# Sheet1.net
KiCad netlist of a schematic drawn in Altium Designer
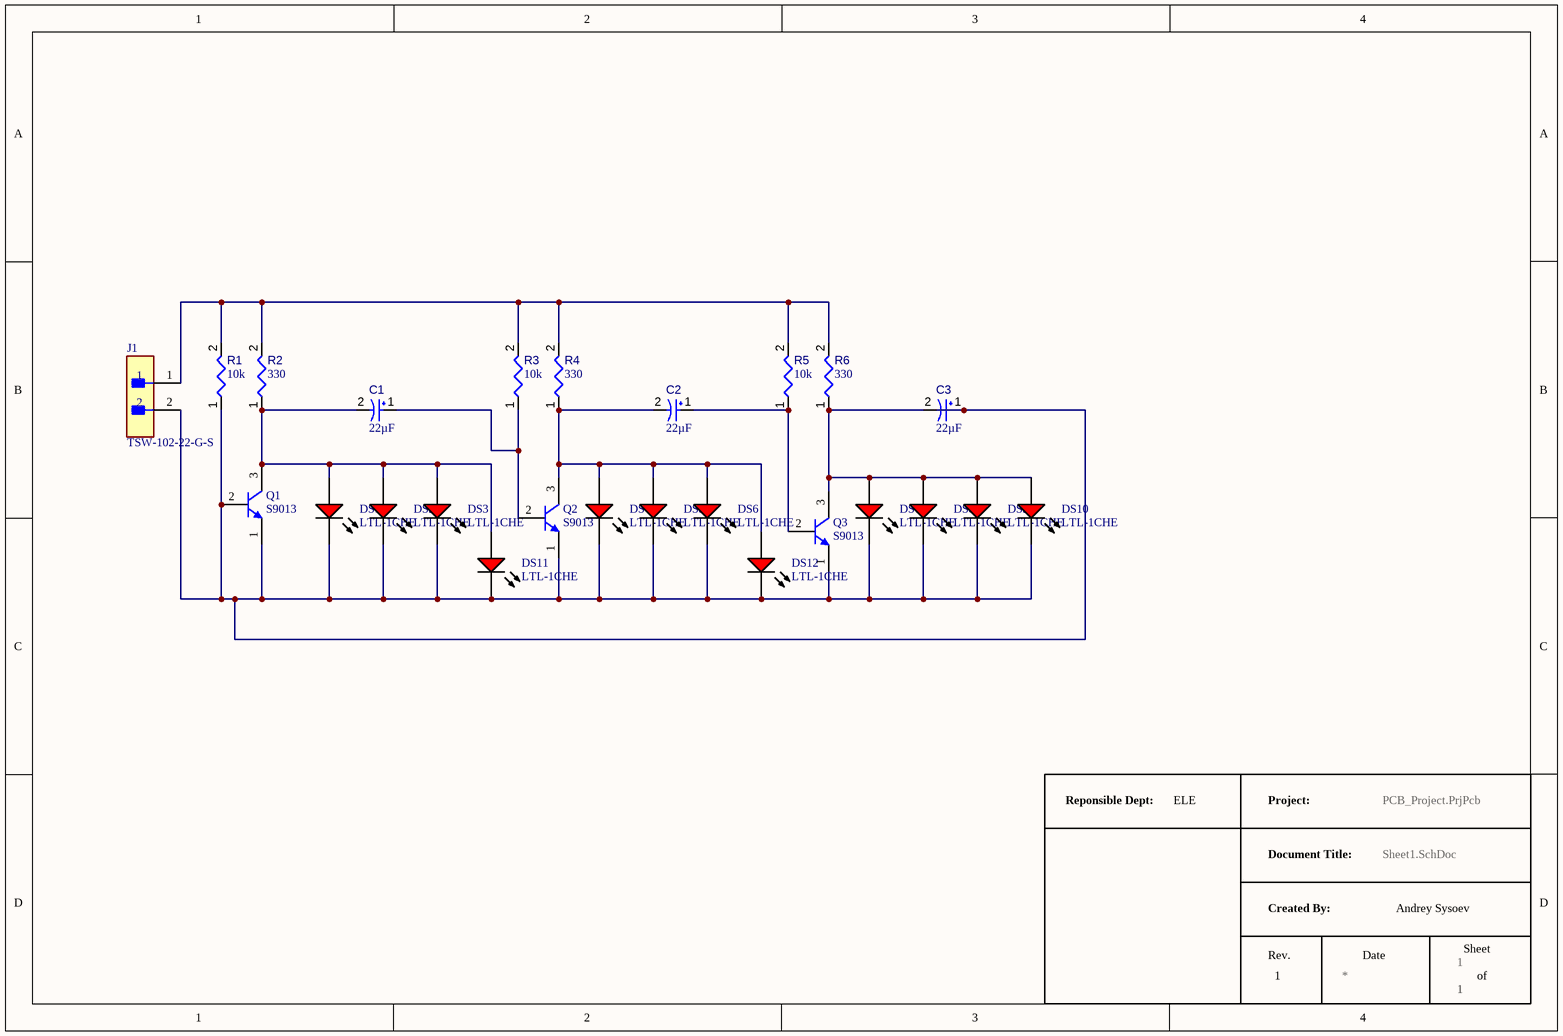
[diagram p0: Sheet1.SchDoc]

(export (version "E")
  (design (tool "Eeschema 10.0.6"))
  (components
    (comp (ref "*") (value "HSHL title block") (libsource (lib "Schlib1") (part "HSHL title block")))
    (comp (ref "C1")
      (value "22µF")
      (footprint "CAPPR55-250-1120X630X1220")
      (description "Aluminum Electrolytic Capacitor, 22 uF, +/- 20%, 100 V, -40 to 85 degC, 2-Pin THD, RoHS, Bulk")
      (fields (field (name "MANUFACTURER") "Panasonic") (field (name "TOLERANCE") "20%"))
      (libsource (lib "Andrey Sysoev") (part "CAP-P-2"))
    )
    (comp (ref "C2")
      (value "22µF")
      (footprint "CAPPR55-250-1120X630X1220")
      (description "Aluminum Electrolytic Capacitor, 22 uF, +/- 20%, 100 V, -40 to 85 degC, 2-Pin THD, RoHS, Bulk")
      (fields (field (name "MANUFACTURER") "Panasonic") (field (name "TOLERANCE") "20%"))
      (libsource (lib "Andrey Sysoev") (part "CAP-P-2"))
    )
    (comp (ref "C3")
      (value "22µF")
      (footprint "CAPPR55-250-1120X630X1220")
      (description "Aluminum Electrolytic Capacitor, 22 uF, +/- 20%, 100 V, -40 to 85 degC, 2-Pin THD, RoHS, Bulk")
      (fields (field (name "MANUFACTURER") "Panasonic") (field (name "TOLERANCE") "20%"))
      (libsource (lib "Andrey Sysoev") (part "CAP-P-2"))
    )
    (comp (ref "DS1")
      (value "LTL-1CHE")
      (footprint "INDPR60-254-520X380X650")
      (description "LED Uni-Color Red, 100 mW, 30 mA, -55 to 100 degC, 2-Pin THD, RoHS, Bulk")
      (fields (field (name "MANUFACTURER") "Lite-On"))
      (libsource (lib "Andrey Sysoev") (part "LED-RED-AK-2"))
    )
    (comp (ref "DS2")
      (value "LTL-1CHE")
      (footprint "INDPR60-254-520X380X650")
      (description "LED Uni-Color Red, 100 mW, 30 mA, -55 to 100 degC, 2-Pin THD, RoHS, Bulk")
      (fields (field (name "MANUFACTURER") "Lite-On"))
      (libsource (lib "Andrey Sysoev") (part "LED-RED-AK-2"))
    )
    (comp (ref "DS3")
      (value "LTL-1CHE")
      (footprint "INDPR60-254-520X380X650")
      (description "LED Uni-Color Red, 100 mW, 30 mA, -55 to 100 degC, 2-Pin THD, RoHS, Bulk")
      (fields (field (name "MANUFACTURER") "Lite-On"))
      (libsource (lib "Andrey Sysoev") (part "LED-RED-AK-2"))
    )
    (comp (ref "DS4")
      (value "LTL-1CHE")
      (footprint "INDPR60-254-520X380X650")
      (description "LED Uni-Color Red, 100 mW, 30 mA, -55 to 100 degC, 2-Pin THD, RoHS, Bulk")
      (fields (field (name "MANUFACTURER") "Lite-On"))
      (libsource (lib "Andrey Sysoev") (part "LED-RED-AK-2"))
    )
    (comp (ref "DS5")
      (value "LTL-1CHE")
      (footprint "INDPR60-254-520X380X650")
      (description "LED Uni-Color Red, 100 mW, 30 mA, -55 to 100 degC, 2-Pin THD, RoHS, Bulk")
      (fields (field (name "MANUFACTURER") "Lite-On"))
      (libsource (lib "Andrey Sysoev") (part "LED-RED-AK-2"))
    )
    (comp (ref "DS6")
      (value "LTL-1CHE")
      (footprint "INDPR60-254-520X380X650")
      (description "LED Uni-Color Red, 100 mW, 30 mA, -55 to 100 degC, 2-Pin THD, RoHS, Bulk")
      (fields (field (name "MANUFACTURER") "Lite-On"))
      (libsource (lib "Andrey Sysoev") (part "LED-RED-AK-2"))
    )
    (comp (ref "DS7")
      (value "LTL-1CHE")
      (footprint "INDPR60-254-520X380X650")
      (description "LED Uni-Color Red, 100 mW, 30 mA, -55 to 100 degC, 2-Pin THD, RoHS, Bulk")
      (fields (field (name "MANUFACTURER") "Lite-On"))
      (libsource (lib "Andrey Sysoev") (part "LED-RED-AK-2"))
    )
    (comp (ref "DS8")
      (value "LTL-1CHE")
      (footprint "INDPR60-254-520X380X650")
      (description "LED Uni-Color Red, 100 mW, 30 mA, -55 to 100 degC, 2-Pin THD, RoHS, Bulk")
      (fields (field (name "MANUFACTURER") "Lite-On"))
      (libsource (lib "Andrey Sysoev") (part "LED-RED-AK-2"))
    )
    (comp (ref "DS9")
      (value "LTL-1CHE")
      (footprint "INDPR60-254-520X380X650")
      (description "LED Uni-Color Red, 100 mW, 30 mA, -55 to 100 degC, 2-Pin THD, RoHS, Bulk")
      (fields (field (name "MANUFACTURER") "Lite-On"))
      (libsource (lib "Andrey Sysoev") (part "LED-RED-AK-2"))
    )
    (comp (ref "DS10")
      (value "LTL-1CHE")
      (footprint "INDPR60-254-520X380X650")
      (description "LED Uni-Color Red, 100 mW, 30 mA, -55 to 100 degC, 2-Pin THD, RoHS, Bulk")
      (fields (field (name "MANUFACTURER") "Lite-On"))
      (libsource (lib "Andrey Sysoev") (part "LED-RED-AK-2"))
    )
    (comp (ref "DS11")
      (value "LTL-1CHE")
      (footprint "INDPR60-254-520X380X650")
      (description "LED Uni-Color Red, 100 mW, 30 mA, -55 to 100 degC, 2-Pin THD, RoHS, Bulk")
      (fields (field (name "MANUFACTURER") "Lite-On"))
      (libsource (lib "Andrey Sysoev") (part "LED-RED-AK-2"))
    )
    (comp (ref "DS12")
      (value "LTL-1CHE")
      (footprint "INDPR60-254-520X380X650")
      (description "LED Uni-Color Red, 100 mW, 30 mA, -55 to 100 degC, 2-Pin THD, RoHS, Bulk")
      (fields (field (name "MANUFACTURER") "Lite-On"))
      (libsource (lib "Andrey Sysoev") (part "LED-RED-AK-2"))
    )
    (comp (ref "J1")
      (value "TSW-102-22-G-S")
      (footprint "FP-TSW-102-22-G-S-MFG")
      (description "TSW - Samtec 2.54mm Pin Header 16mm Overall Pin Length 7.62mm Tail (22) - Fast Stock(mcv)")
      (libsource (lib "Andrey Sysoev") (part "3bc925449376181038e59eaffc5286c"))
    )
    (comp (ref "Q1")
      (value "S9013")
      (footprint "JSCJ-TO-92-3_V")
      (description "Transistor, NPN, 0.1 uA, 150 MHz, 3-Pin TO-92")
      (fields (field (name "MANUFACTURER") "Jiangsu Changjiang Electronics Technology"))
      (libsource (lib "Andrey Sysoev") (part "BJT-NPN-EBC-3"))
    )
    (comp (ref "Q2")
      (value "S9013")
      (footprint "JSCJ-TO-92-3_V")
      (description "Transistor, NPN, 0.1 uA, 150 MHz, 3-Pin TO-92")
      (fields (field (name "MANUFACTURER") "Jiangsu Changjiang Electronics Technology"))
      (libsource (lib "Andrey Sysoev") (part "BJT-NPN-EBC-3"))
    )
    (comp (ref "Q3")
      (value "S9013")
      (footprint "JSCJ-TO-92-3_V")
      (description "Transistor, NPN, 0.1 uA, 150 MHz, 3-Pin TO-92")
      (fields (field (name "MANUFACTURER") "Jiangsu Changjiang Electronics Technology"))
      (libsource (lib "Andrey Sysoev") (part "BJT-NPN-EBC-3"))
    )
    (comp (ref "R1")
      (value "10k")
      (footprint "RESA60-630X240")
      (description "Axial Resistor, 10 KOhm, +/- 1%, 0.25 W, -55 to 155 degC, 2-Pin THD, RoHS, Bulk")
      (fields (field (name "TOLERANCE") "1%") (field (name "POWER") "250mW"))
      (libsource (lib "Andrey Sysoev") (part "RES-2"))
    )
    (comp (ref "R2")
      (value "330")
      (footprint "STA_CF18_STP")
      (description "Fixed Resistor, Carbon Film, 0.125W, 330ohm, 250V, 5% +/-Tol, -400, 0ppm/Cel, Through Hole Mount")
      (fields (field (name "TOLERANCE") "5%") (field (name "Comment") "CF18JT330R"))
      (libsource (lib "Andrey Sysoev") (part "RES-2"))
    )
    (comp (ref "R3")
      (value "10k")
      (footprint "RESA60-630X240")
      (description "Axial Resistor, 10 KOhm, +/- 1%, 0.25 W, -55 to 155 degC, 2-Pin THD, RoHS, Bulk")
      (fields (field (name "TOLERANCE") "1%") (field (name "POWER") "250mW"))
      (libsource (lib "Andrey Sysoev") (part "RES-2"))
    )
    (comp (ref "R4")
      (value "330")
      (footprint "STA_CF18_STP")
      (description "Fixed Resistor, Carbon Film, 0.125W, 330ohm, 250V, 5% +/-Tol, -400, 0ppm/Cel, Through Hole Mount")
      (fields (field (name "TOLERANCE") "5%") (field (name "Comment") "CF18JT330R"))
      (libsource (lib "Andrey Sysoev") (part "RES-2"))
    )
    (comp (ref "R5")
      (value "10k")
      (footprint "RESA60-630X240")
      (description "Axial Resistor, 10 KOhm, +/- 1%, 0.25 W, -55 to 155 degC, 2-Pin THD, RoHS, Bulk")
      (fields (field (name "TOLERANCE") "1%") (field (name "POWER") "250mW"))
      (libsource (lib "Andrey Sysoev") (part "RES-2"))
    )
    (comp (ref "R6")
      (value "330")
      (footprint "STA_CF18_STP")
      (description "Fixed Resistor, Carbon Film, 0.125W, 330ohm, 250V, 5% +/-Tol, -400, 0ppm/Cel, Through Hole Mount")
      (fields (field (name "TOLERANCE") "5%") (field (name "Comment") "CF18JT330R"))
      (libsource (lib "Andrey Sysoev") (part "RES-2"))
    )
  )
  (nets
    (net (code "1") (name "Net-(DS1-A)") (class "Default")
      (node (ref "C1") (pin "2") (pinfunction "2_2") (pintype "passive"))
      (node (ref "DS1") (pin "1") (pinfunction "A_1") (pintype "passive"))
      (node (ref "DS11") (pin "1") (pinfunction "A_1") (pintype "passive"))
      (node (ref "DS2") (pin "1") (pinfunction "A_1") (pintype "passive"))
      (node (ref "DS3") (pin "1") (pinfunction "A_1") (pintype "passive"))
      (node (ref "Q1") (pin "3") (pinfunction "C_3") (pintype "passive"))
      (node (ref "R2") (pin "1") (pinfunction "1_1") (pintype "passive"))
    )
    (net (code "2") (name "Net-(DS1-K)") (class "Default")
      (node (ref "C3") (pin "1") (pinfunction "1_1") (pintype "passive"))
      (node (ref "DS1") (pin "2") (pinfunction "K_2") (pintype "passive"))
      (node (ref "DS10") (pin "2") (pinfunction "K_2") (pintype "passive"))
      (node (ref "DS11") (pin "2") (pinfunction "K_2") (pintype "passive"))
      (node (ref "DS12") (pin "2") (pinfunction "K_2") (pintype "passive"))
      (node (ref "DS2") (pin "2") (pinfunction "K_2") (pintype "passive"))
      (node (ref "DS3") (pin "2") (pinfunction "K_2") (pintype "passive"))
      (node (ref "DS4") (pin "2") (pinfunction "K_2") (pintype "passive"))
      (node (ref "DS5") (pin "2") (pinfunction "K_2") (pintype "passive"))
      (node (ref "DS6") (pin "2") (pinfunction "K_2") (pintype "passive"))
      (node (ref "DS7") (pin "2") (pinfunction "K_2") (pintype "passive"))
      (node (ref "DS8") (pin "2") (pinfunction "K_2") (pintype "passive"))
      (node (ref "DS9") (pin "2") (pinfunction "K_2") (pintype "passive"))
      (node (ref "J1") (pin "2") (pinfunction "2_2") (pintype "passive"))
      (node (ref "Q1") (pin "1") (pinfunction "E_1") (pintype "passive"))
      (node (ref "Q1") (pin "2") (pinfunction "B_2") (pintype "passive"))
      (node (ref "Q2") (pin "1") (pinfunction "E_1") (pintype "passive"))
      (node (ref "Q3") (pin "1") (pinfunction "E_1") (pintype "passive"))
      (node (ref "R1") (pin "1") (pinfunction "1_1") (pintype "passive"))
    )
    (net (code "3") (name "Net-(DS10-A)") (class "Default")
      (node (ref "C3") (pin "2") (pinfunction "2_2") (pintype "passive"))
      (node (ref "DS10") (pin "1") (pinfunction "A_1") (pintype "passive"))
      (node (ref "DS7") (pin "1") (pinfunction "A_1") (pintype "passive"))
      (node (ref "DS8") (pin "1") (pinfunction "A_1") (pintype "passive"))
      (node (ref "DS9") (pin "1") (pinfunction "A_1") (pintype "passive"))
      (node (ref "Q3") (pin "3") (pinfunction "C_3") (pintype "passive"))
      (node (ref "R6") (pin "1") (pinfunction "1_1") (pintype "passive"))
    )
    (net (code "4") (name "Net-(DS12-A)") (class "Default")
      (node (ref "C2") (pin "2") (pinfunction "2_2") (pintype "passive"))
      (node (ref "DS12") (pin "1") (pinfunction "A_1") (pintype "passive"))
      (node (ref "DS4") (pin "1") (pinfunction "A_1") (pintype "passive"))
      (node (ref "DS5") (pin "1") (pinfunction "A_1") (pintype "passive"))
      (node (ref "DS6") (pin "1") (pinfunction "A_1") (pintype "passive"))
      (node (ref "Q2") (pin "3") (pinfunction "C_3") (pintype "passive"))
      (node (ref "R4") (pin "1") (pinfunction "1_1") (pintype "passive"))
    )
    (net (code "5") (name "Net-(J1-Pad1)") (class "Default")
      (node (ref "J1") (pin "1") (pinfunction "1_1") (pintype "passive"))
      (node (ref "R1") (pin "2") (pinfunction "2_2") (pintype "passive"))
      (node (ref "R2") (pin "2") (pinfunction "2_2") (pintype "passive"))
      (node (ref "R3") (pin "2") (pinfunction "2_2") (pintype "passive"))
      (node (ref "R4") (pin "2") (pinfunction "2_2") (pintype "passive"))
      (node (ref "R5") (pin "2") (pinfunction "2_2") (pintype "passive"))
      (node (ref "R6") (pin "2") (pinfunction "2_2") (pintype "passive"))
    )
    (net (code "6") (name "Net-(Q2-B)") (class "Default")
      (node (ref "C1") (pin "1") (pinfunction "1_1") (pintype "passive"))
      (node (ref "Q2") (pin "2") (pinfunction "B_2") (pintype "passive"))
      (node (ref "R3") (pin "1") (pinfunction "1_1") (pintype "passive"))
    )
    (net (code "7") (name "Net-(Q3-B)") (class "Default")
      (node (ref "C2") (pin "1") (pinfunction "1_1") (pintype "passive"))
      (node (ref "Q3") (pin "2") (pinfunction "B_2") (pintype "passive"))
      (node (ref "R5") (pin "1") (pinfunction "1_1") (pintype "passive"))
    )
  )
)
